# DCDC.net
KiCad netlist of a schematic drawn in Altium Designer
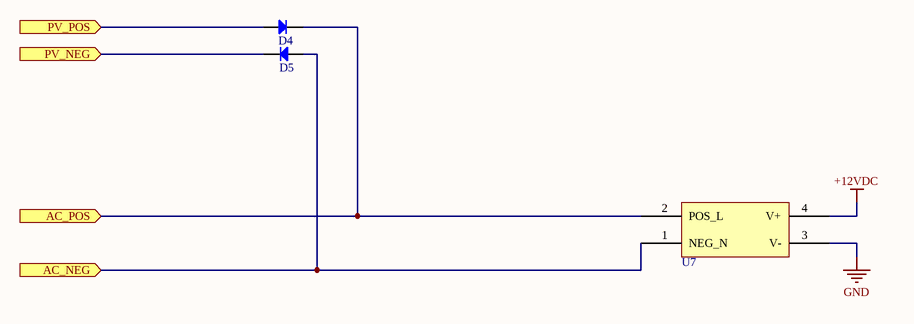
[diagram p0: DCDC.SchDoc]

(export (version "E")
  (design (tool "Eeschema 10.0.6"))
  (components
    (comp (ref "D4")
      (value "S3G-13-F")
      (footprint "SMC DO-214AB")
      (description "DIODE GEN PURP 400V 3A SMC")
      (fields (field (name "MANUFACTURER") "Diodes Incorporated") (field (name "VOLTAGE") "V"))
      (libsource (lib "RELECTRIFY-PARTSlib_A") (part "Diode"))
    )
    (comp (ref "D5")
      (value "S3G-13-F")
      (footprint "SMC DO-214AB")
      (description "DIODE GEN PURP 400V 3A SMC")
      (fields (field (name "MANUFACTURER") "Diodes Incorporated") (field (name "VOLTAGE") "V"))
      (libsource (lib "RELECTRIFY-PARTSlib_A") (part "Diode"))
    )
    (comp (ref "U7")
      (value "EPS-25-12")
      (footprint "EPS-25-12")
      (description "AC/DC CONVERTER 12V 25W")
      (fields (field (name "PARTNUMBER") "1092-0010") (field (name "MANUFACTURER") "MEAN WELL USA Inc."))
      (libsource (lib "RELECTRIFY-PARTSlib_A") (part "EPS-25-12"))
    )
  )
  (nets
    (net (code "1") (name "+12VDC") (class "Default")
      (node (ref "U7") (pin "4") (pinfunction "V+_4") (pintype "passive"))
    )
    (net (code "2") (name "/AC_NEG") (class "Default")
      (node (ref "D5") (pin "A") (pinfunction "A_A") (pintype "passive"))
      (node (ref "U7") (pin "1") (pinfunction "NEG_N_1") (pintype "passive"))
    )
    (net (code "3") (name "/AC_POS") (class "Default")
      (node (ref "D4") (pin "K") (pinfunction "K_K") (pintype "passive"))
      (node (ref "U7") (pin "2") (pinfunction "POS_L_2") (pintype "passive"))
    )
    (net (code "4") (name "/PV_NEG") (class "Default")
      (node (ref "D5") (pin "K") (pinfunction "K_K") (pintype "passive"))
    )
    (net (code "5") (name "/PV_POS") (class "Default")
      (node (ref "D4") (pin "A") (pinfunction "A_A") (pintype "passive"))
    )
    (net (code "6") (name "GND") (class "Default")
      (node (ref "U7") (pin "3") (pinfunction "V-_3") (pintype "passive"))
    )
  )
)
